# Display.net
KiCad netlist of a schematic drawn in Altium Designer
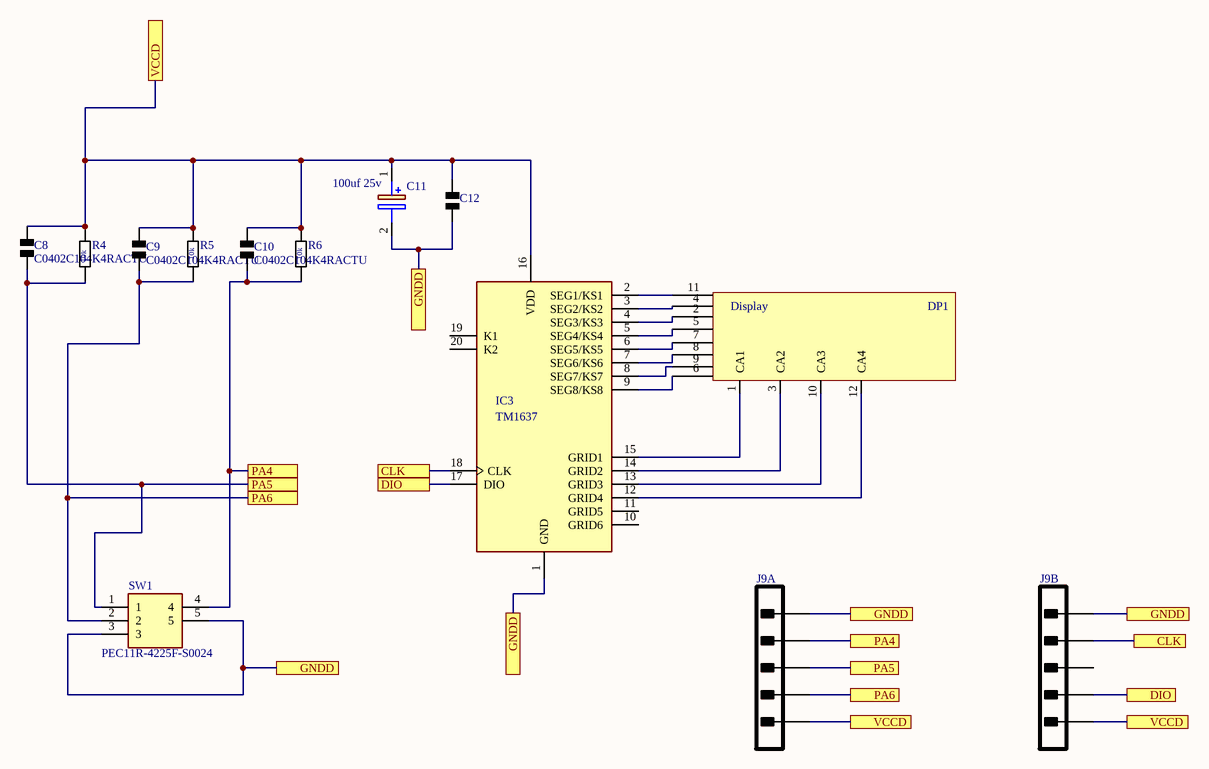
[diagram p0: Display.SchDoc]

(export (version "E")
  (design (tool "Eeschema 10.0.6"))
  (components
    (comp (ref "C8")
      (value "C0402C104K4RACTU")
      (footprint "Capacitor")
      (fields (field (name "MANUFACTURER") "Kemet"))
      (libsource (lib "Soldeer Station Library") (part "Condensator"))
    )
    (comp (ref "C9")
      (value "C0402C104K4RACTU")
      (footprint "Capacitor")
      (fields (field (name "MANUFACTURER") "Kemet"))
      (libsource (lib "Soldeer Station Library") (part "Condensator"))
    )
    (comp (ref "C10")
      (value "C0402C104K4RACTU")
      (footprint "Capacitor")
      (fields (field (name "MANUFACTURER") "Kemet"))
      (libsource (lib "Soldeer Station Library") (part "Condensator"))
    )
    (comp (ref "C11")
      (value "100uf 25v")
      (footprint "100uf 25v")
      (description "Capacitor Polarised")
      (fields
        (field (name "MANUFACTURER_PART_NUMBER") "ESMG250ELL101MF11D")
        (field (name "MOUSER PART NUMBER") "661-ESMG250ELL101MF")
      )
      (libsource (lib "Soldeer Station Library") (part "100uf 25v"))
    )
    (comp (ref "C12")
      (value "C0402C104K4RACTU")
      (footprint "Capacitor")
      (fields (field (name "MANUFACTURER") "Kemet"))
      (libsource (lib "Soldeer Station Library") (part "Condensator"))
    )
    (comp (ref "DP1")
      (value "Display")
      (footprint "DIP12")
      (libsource (lib "Soldeer Station Library") (part "Display"))
    )
    (comp (ref "IC3")
      (value "TM1637")
      (footprint "TM1637")
      (fields (field (name "MF") "Titan Micro Electronics"))
      (libsource (lib "Soldeer Station Library") (part "TM1637"))
    )
    (comp (ref "J9A")
      (value "K9 5Pinheader")
      (footprint "K9 5Pinheader")
      (libsource (lib "Soldeer Station Library") (part "K9 5Pinheader"))
    )
    (comp (ref "J9B")
      (value "K9 5Pinheader")
      (footprint "K9 5Pinheader")
      (libsource (lib "Soldeer Station Library") (part "K9 5Pinheader"))
    )
    (comp (ref "R4")
      (value "10k")
      (footprint "Resistor")
      (fields (field (name "MANUFACTURER") "Vishay Dale") (field (name "PART NUMBER") "CRCW08050000Z0EA"))
      (libsource (lib "Soldeer Station Library") (part "Resistor"))
    )
    (comp (ref "R5")
      (value "10k")
      (footprint "Resistor")
      (fields (field (name "MANUFACTURER") "Vishay Dale") (field (name "PART NUMBER") "CRCW08050000Z0EA"))
      (libsource (lib "Soldeer Station Library") (part "Resistor"))
    )
    (comp (ref "R6")
      (value "10k")
      (footprint "Resistor")
      (fields (field (name "MANUFACTURER") "Vishay Dale") (field (name "PART NUMBER") "CRCW08050000Z0EA"))
      (libsource (lib "Soldeer Station Library") (part "Resistor"))
    )
    (comp (ref "SW1")
      (value "PEC11R-4225F-S0024")
      (footprint "PEC11 S1")
      (description "Undefined or Miscellaneous")
      (fields (field (name "MOUSER PART NUMBER") "652-PEC11R-4225F-S24"))
      (libsource (lib "*") (part "PEC11R-4225F-S0024"))
    )
  )
  (nets
    (net (code "1") (name "/CLK") (class "Default")
      (node (ref "IC3") (pin "18") (pinfunction "CLK_18") (pintype "passive"))
      (node (ref "J9B") (pin "2") (pinfunction "2_2") (pintype "passive"))
    )
    (net (code "2") (name "/DIO") (class "Default")
      (node (ref "IC3") (pin "17") (pinfunction "DIO_17") (pintype "passive"))
      (node (ref "J9B") (pin "4") (pinfunction "4_4") (pintype "passive"))
    )
    (net (code "3") (name "/GNDD") (class "Default")
      (node (ref "C11") (pin "2") (pinfunction "-_2") (pintype "passive"))
      (node (ref "C12") (pin "1") (pinfunction "1_1") (pintype "passive"))
      (node (ref "IC3") (pin "1") (pinfunction "GND_1") (pintype "power_in"))
      (node (ref "J9A") (pin "1") (pinfunction "1_1") (pintype "passive"))
      (node (ref "J9B") (pin "1") (pinfunction "1_1") (pintype "passive"))
      (node (ref "SW1") (pin "3") (pinfunction "3_3") (pintype "passive"))
      (node (ref "SW1") (pin "5") (pinfunction "5_5") (pintype "passive"))
    )
    (net (code "4") (name "/PA4") (class "Default")
      (node (ref "C10") (pin "1") (pinfunction "1_1") (pintype "passive"))
      (node (ref "J9A") (pin "2") (pinfunction "2_2") (pintype "passive"))
      (node (ref "R6") (pin "1") (pinfunction "1_1") (pintype "passive"))
      (node (ref "SW1") (pin "4") (pinfunction "4_4") (pintype "passive"))
    )
    (net (code "5") (name "/PA5") (class "Default")
      (node (ref "C8") (pin "1") (pinfunction "1_1") (pintype "passive"))
      (node (ref "J9A") (pin "3") (pinfunction "3_3") (pintype "passive"))
      (node (ref "R4") (pin "1") (pinfunction "1_1") (pintype "passive"))
      (node (ref "SW1") (pin "1") (pinfunction "1_1") (pintype "passive"))
    )
    (net (code "6") (name "/PA6") (class "Default")
      (node (ref "C9") (pin "1") (pinfunction "1_1") (pintype "passive"))
      (node (ref "J9A") (pin "4") (pinfunction "4_4") (pintype "passive"))
      (node (ref "R5") (pin "1") (pinfunction "1_1") (pintype "passive"))
      (node (ref "SW1") (pin "2") (pinfunction "2_2") (pintype "passive"))
    )
    (net (code "7") (name "/VCCD") (class "Default")
      (node (ref "C10") (pin "2") (pinfunction "2_2") (pintype "passive"))
      (node (ref "C11") (pin "1") (pinfunction "+_1") (pintype "passive"))
      (node (ref "C12") (pin "2") (pinfunction "2_2") (pintype "passive"))
      (node (ref "C8") (pin "2") (pinfunction "2_2") (pintype "passive"))
      (node (ref "C9") (pin "2") (pinfunction "2_2") (pintype "passive"))
      (node (ref "IC3") (pin "16") (pinfunction "VDD_16") (pintype "power_in"))
      (node (ref "J9A") (pin "5") (pinfunction "5_5") (pintype "passive"))
      (node (ref "J9B") (pin "5") (pinfunction "5_5") (pintype "passive"))
      (node (ref "R4") (pin "2") (pinfunction "2_2") (pintype "passive"))
      (node (ref "R5") (pin "2") (pinfunction "2_2") (pintype "passive"))
      (node (ref "R6") (pin "2") (pinfunction "2_2") (pintype "passive"))
    )
    (net (code "8") (name "Net-(DP1-CA1)") (class "Default")
      (node (ref "DP1") (pin "1") (pinfunction "CA1_1") (pintype "passive"))
      (node (ref "IC3") (pin "15") (pinfunction "GRID1_15") (pintype "passive"))
    )
    (net (code "9") (name "Net-(DP1-CA2)") (class "Default")
      (node (ref "DP1") (pin "3") (pinfunction "CA2_3") (pintype "passive"))
      (node (ref "IC3") (pin "14") (pinfunction "GRID2_14") (pintype "passive"))
    )
    (net (code "10") (name "Net-(DP1-CA3)") (class "Default")
      (node (ref "DP1") (pin "10") (pinfunction "CA3_10") (pintype "passive"))
      (node (ref "IC3") (pin "13") (pinfunction "GRID3_13") (pintype "passive"))
    )
    (net (code "11") (name "Net-(DP1-CA4)") (class "Default")
      (node (ref "DP1") (pin "12") (pinfunction "CA4_12") (pintype "passive"))
      (node (ref "IC3") (pin "12") (pinfunction "GRID4_12") (pintype "passive"))
    )
    (net (code "12") (name "Net-(IC3-SEG1{slash}KS1)") (class "Default")
      (node (ref "DP1") (pin "11") (pintype "passive"))
      (node (ref "IC3") (pin "2") (pinfunction "SEG1/KS1_2") (pintype "passive"))
    )
    (net (code "13") (name "Net-(IC3-SEG2{slash}KS2)") (class "Default")
      (node (ref "DP1") (pin "4") (pintype "passive"))
      (node (ref "IC3") (pin "3") (pinfunction "SEG2/KS2_3") (pintype "passive"))
    )
    (net (code "14") (name "Net-(IC3-SEG3{slash}KS3)") (class "Default")
      (node (ref "DP1") (pin "2") (pintype "passive"))
      (node (ref "IC3") (pin "4") (pinfunction "SEG3/KS3_4") (pintype "passive"))
    )
    (net (code "15") (name "Net-(IC3-SEG4{slash}KS4)") (class "Default")
      (node (ref "DP1") (pin "5") (pintype "passive"))
      (node (ref "IC3") (pin "5") (pinfunction "SEG4/KS4_5") (pintype "passive"))
    )
    (net (code "16") (name "Net-(IC3-SEG5{slash}KS5)") (class "Default")
      (node (ref "DP1") (pin "7") (pintype "passive"))
      (node (ref "IC3") (pin "6") (pinfunction "SEG5/KS5_6") (pintype "passive"))
    )
    (net (code "17") (name "Net-(IC3-SEG6{slash}KS6)") (class "Default")
      (node (ref "DP1") (pin "8") (pintype "passive"))
      (node (ref "IC3") (pin "7") (pinfunction "SEG6/KS6_7") (pintype "passive"))
    )
    (net (code "18") (name "Net-(IC3-SEG7{slash}KS7)") (class "Default")
      (node (ref "DP1") (pin "9") (pintype "passive"))
      (node (ref "IC3") (pin "8") (pinfunction "SEG7/KS7_8") (pintype "passive"))
    )
    (net (code "19") (name "Net-(IC3-SEG8{slash}KS8)") (class "Default")
      (node (ref "DP1") (pin "6") (pintype "passive"))
      (node (ref "IC3") (pin "9") (pinfunction "SEG8/KS8_9") (pintype "passive"))
    )
    (net (code "20") (name "unconnected-(IC3-GRID5-Pad11)") (class "Default")
      (node (ref "IC3") (pin "11") (pinfunction "GRID5_11") (pintype "passive"))
    )
    (net (code "21") (name "unconnected-(IC3-GRID6-Pad10)") (class "Default")
      (node (ref "IC3") (pin "10") (pinfunction "GRID6_10") (pintype "passive"))
    )
    (net (code "22") (name "unconnected-(IC3-K1-Pad19)") (class "Default")
      (node (ref "IC3") (pin "19") (pinfunction "K1_19") (pintype "passive"))
    )
    (net (code "23") (name "unconnected-(IC3-K2-Pad20)") (class "Default")
      (node (ref "IC3") (pin "20") (pinfunction "K2_20") (pintype "passive"))
    )
    (net (code "24") (name "unconnected-(J9B-Pad3)") (class "Default")
      (node (ref "J9B") (pin "3") (pinfunction "3_3") (pintype "passive"))
    )
  )
)
